# CH32V002F4P6.net
KiCad netlist of a schematic drawn in Altium Designer
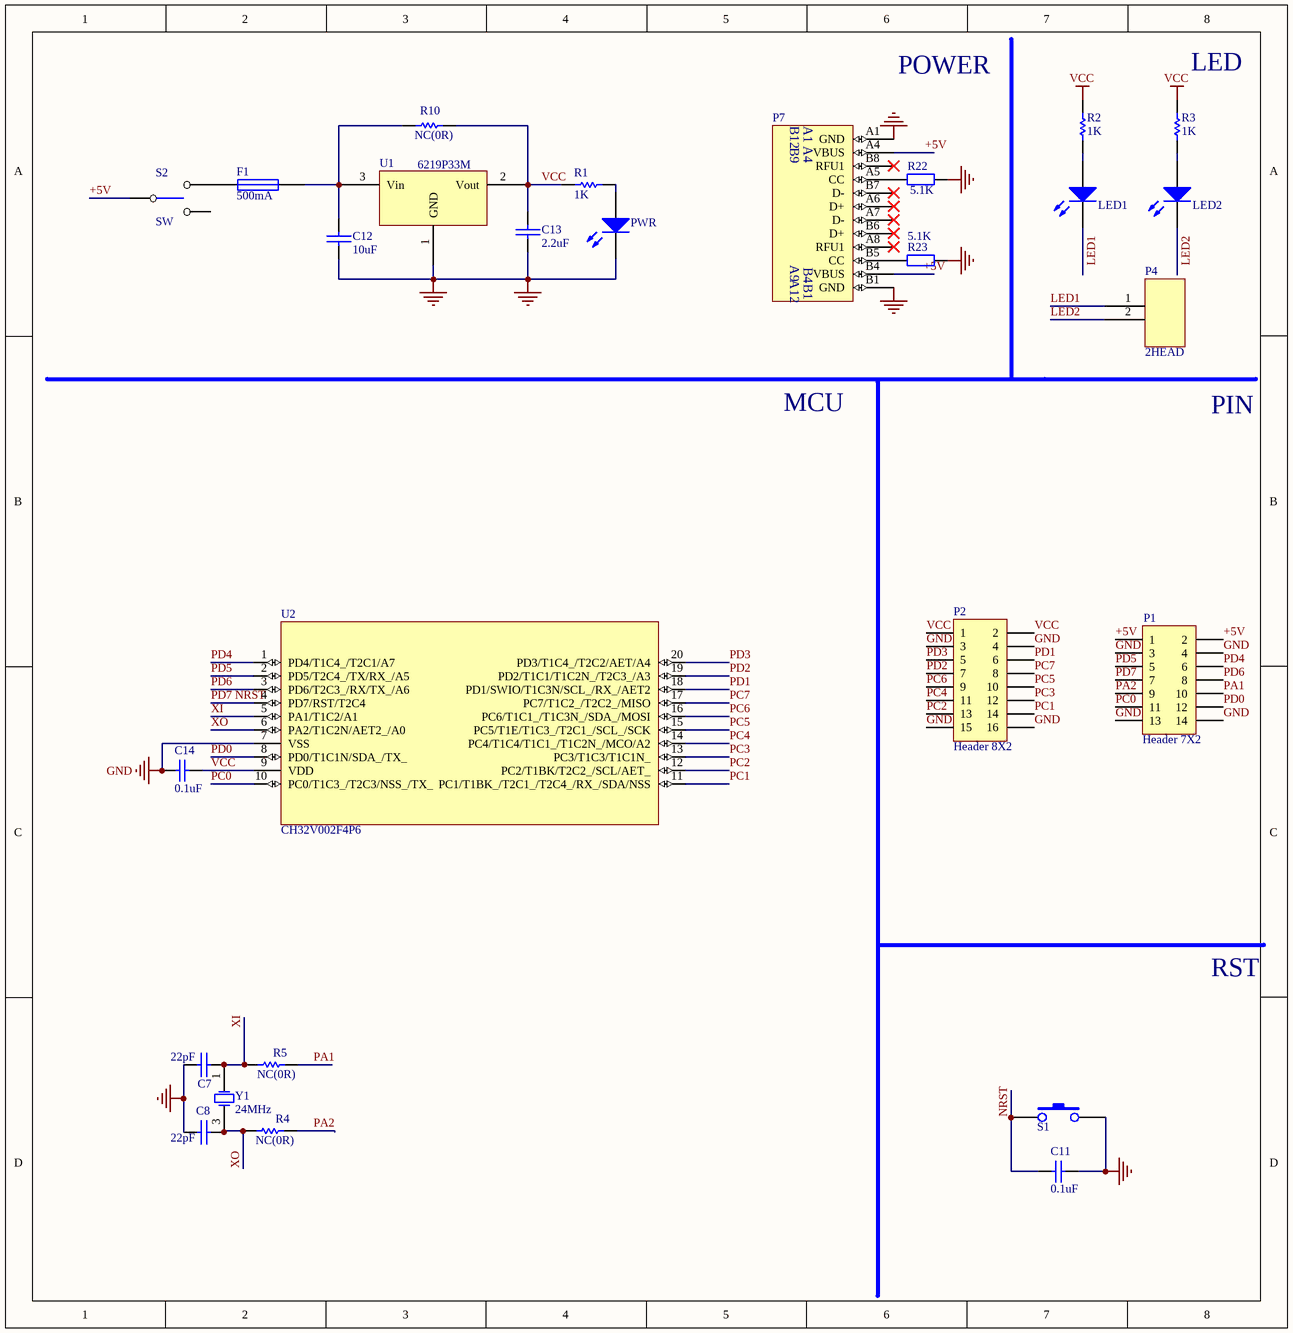
[diagram p0: CH32V002F4P6.SchDoc]

(export (version "E")
  (design (tool "Eeschema 10.0.6"))
  (components
    (comp (ref "C7")
      (value "22pF")
      (footprint "0402_C")
      (description "Capacitor")
      (libsource (lib "*") (part "CAP"))
    )
    (comp (ref "C8")
      (value "22pF")
      (footprint "0402_C")
      (description "Capacitor")
      (libsource (lib "*") (part "CAP"))
    )
    (comp (ref "C11")
      (value "0.1uF")
      (footprint "0402_C")
      (description "Capacitor")
      (fields (field (name "PUBLISHER") "Altium Limited"))
      (libsource (lib "*") (part "Cap"))
    )
    (comp (ref "C12")
      (value "10uF")
      (footprint "0603_C")
      (description "Capacitor")
      (libsource (lib "wch_sch_others") (part "CAP"))
    )
    (comp (ref "C13")
      (value "2.2uF")
      (footprint "0402_C")
      (description "Capacitor")
      (libsource (lib "wch_sch_others") (part "CAP"))
    )
    (comp (ref "C14")
      (value "0.1uF")
      (footprint "0603_C")
      (description "Capacitor")
      (fields (field (name "PUBLISHER") "Altium Limited"))
      (libsource (lib "*") (part "Cap"))
    )
    (comp (ref "F1")
      (value "500mA")
      (footprint "0603")
      (description "Fuse")
      (libsource (lib "*") (part "FUSE1"))
    )
    (comp (ref "LED1")
      (value "LED1   blue")
      (footprint "0603+")
      (description "Typical INFRARED GaAs LED")
      (fields (field (name "PUBLISHER") "Altium Limited"))
      (libsource (lib "*") (part "LED0"))
    )
    (comp (ref "LED2")
      (value "LED2  blue")
      (footprint "0603+")
      (description "Typical INFRARED GaAs LED")
      (fields (field (name "PUBLISHER") "Altium Limited"))
      (libsource (lib "*") (part "LED0"))
    )
    (comp (ref "P1")
      (value "Header 7X2")
      (footprint "HDR2X7")
      (description "Header, 7-Pin, Dual row")
      (fields (field (name "PUBLISHER") "Altium Limited"))
      (libsource (lib "Miscellaneous Connectors") (part "Header 7X2"))
    )
    (comp (ref "P2")
      (value "Header 8X2")
      (footprint "HDR2X8")
      (description "Header, 8-Pin, Dual row")
      (fields (field (name "PUBLISHER") "Altium Limited"))
      (libsource (lib "Miscellaneous Connectors") (part "Header 8X2"))
    )
    (comp (ref "P4") (value "2HEAD") (footprint "SIP2-2.54mm") (libsource (lib "*") (part "2HEAD")))
    (comp (ref "P7")
      (value "TYPE-C")
      (footprint "TYPE-C-Receptacle-2.0")
      (libsource (lib "*") (part "TYPE-C1"))
    )
    (comp (ref "PWR")
      (value "POWER  red")
      (footprint "0603+")
      (description "Typical INFRARED GaAs LED")
      (fields (field (name "PUBLISHER") "Altium Limited"))
      (libsource (lib "") (part "LED0_1"))
    )
    (comp (ref "R1")
      (value "1K")
      (footprint "0402")
      (description "Semiconductor Resistor")
      (fields (field (name "PUBLISHER") "Altium Limited"))
      (libsource (lib "*") (part "Res Semi"))
    )
    (comp (ref "R2")
      (value "1K")
      (footprint "0402")
      (description "Semiconductor Resistor")
      (fields (field (name "PUBLISHER") "Altium Limited"))
      (libsource (lib "*") (part "Res Semi"))
    )
    (comp (ref "R3")
      (value "1K")
      (footprint "0402")
      (description "Semiconductor Resistor")
      (fields (field (name "PUBLISHER") "Altium Limited"))
      (libsource (lib "*") (part "Res Semi"))
    )
    (comp (ref "R4")
      (value "NC(0R)")
      (footprint "0402")
      (description "Semiconductor Resistor")
      (fields (field (name "Comment") "0R") (field (name "PUBLISHER") "Altium Limited"))
      (libsource (lib "*") (part "Res Semi"))
    )
    (comp (ref "R5")
      (value "NC(0R)")
      (footprint "0402")
      (description "Semiconductor Resistor")
      (fields (field (name "Comment") "0R") (field (name "PUBLISHER") "Altium Limited"))
      (libsource (lib "*") (part "Res Semi"))
    )
    (comp (ref "R10")
      (value "NC(0R)")
      (footprint "0402")
      (description "Semiconductor Resistor")
      (fields (field (name "Comment") "0R") (field (name "PUBLISHER") "Altium Limited"))
      (libsource (lib "*") (part "Res Semi"))
    )
    (comp (ref "R22")
      (value "5.1K")
      (footprint "0402")
      (description "Resistor")
      (libsource (lib "Miscellaneous Devices") (part "Res2"))
    )
    (comp (ref "R23")
      (value "5.1K")
      (footprint "0402")
      (description "Resistor")
      (libsource (lib "Miscellaneous Devices") (part "Res2"))
    )
    (comp (ref "S1") (value "NRST") (footprint "SMD_6.1x3.65x2.5mm-KEY") (libsource (lib "*") (part "KEY")))
    (comp (ref "S2") (value "SW") (footprint "SW1") (libsource (lib "*") (part "SW")))
    (comp (ref "U1")
      (value "6219P33M")
      (footprint "SOT-23")
      (libsource (lib "wch_sch_others") (part "6219P33M"))
    )
    (comp (ref "U2")
      (value "CH32V002F4P6")
      (footprint "TSSOP20")
      (description "RISC-V MCU, 48MHz, ADC/UART/I2C/SPI")
      (libsource (lib "DHXXXSCH") (part "CH32V002F4P6"))
    )
    (comp (ref "Y1")
      (value "24MHz")
      (footprint "XT3225")
      (description "Crystal Oscillator")
      (fields (field (name "PUBLISHER") "Altium Limited"))
      (libsource (lib "*") (part "XTAL"))
    )
  )
  (nets
    (net (code "1") (name "/+5V") (class "Default")
      (node (ref "P1") (pin "1") (pinfunction "1_1") (pintype "passive"))
      (node (ref "P1") (pin "2") (pinfunction "2_2") (pintype "passive"))
      (node (ref "P7") (pin "A4") (pinfunction "VBUS_A4") (pintype "bidirectional"))
      (node (ref "P7") (pin "B4") (pinfunction "VBUS_B4") (pintype "bidirectional"))
      (node (ref "S2") (pin "1") (pinfunction "1_1") (pintype "passive"))
    )
    (net (code "2") (name "/LED1") (class "Default")
      (node (ref "LED1") (pin "2") (pinfunction "K_2") (pintype "passive"))
      (node (ref "P4") (pin "1") (pintype "passive"))
    )
    (net (code "3") (name "/LED2") (class "Default")
      (node (ref "LED2") (pin "2") (pinfunction "K_2") (pintype "passive"))
      (node (ref "P4") (pin "2") (pintype "passive"))
    )
    (net (code "4") (name "/NRST") (class "Default")
      (node (ref "C11") (pin "2") (pinfunction "2_2") (pintype "passive"))
      (node (ref "P1") (pin "7") (pinfunction "7_7") (pintype "passive"))
      (node (ref "S1") (pin "1") (pinfunction "1_1") (pintype "passive"))
      (node (ref "U2") (pin "4") (pinfunction "PD7/RST/T2C4_4") (pintype "bidirectional"))
    )
    (net (code "5") (name "/PA1") (class "Default")
      (node (ref "P1") (pin "10") (pinfunction "10_10") (pintype "passive"))
      (node (ref "R5") (pin "2") (pinfunction "2_2") (pintype "passive"))
    )
    (net (code "6") (name "/PA2") (class "Default")
      (node (ref "P1") (pin "9") (pinfunction "9_9") (pintype "passive"))
      (node (ref "R4") (pin "2") (pinfunction "2_2") (pintype "passive"))
    )
    (net (code "7") (name "/PC0") (class "Default")
      (node (ref "P1") (pin "11") (pinfunction "11_11") (pintype "passive"))
      (node (ref "U2") (pin "10") (pinfunction "PC0/T1C3_/T2C3/NSS_/TX__10") (pintype "bidirectional"))
    )
    (net (code "8") (name "/PC1") (class "Default")
      (node (ref "P2") (pin "14") (pinfunction "14_14") (pintype "passive"))
      (node (ref "U2") (pin "11") (pinfunction "PC1/T1BK_/T2C1_/T2C4_/RX_/SDA/NSS_11") (pintype "bidirectional"))
    )
    (net (code "9") (name "/PC2") (class "Default")
      (node (ref "P2") (pin "13") (pinfunction "13_13") (pintype "passive"))
      (node (ref "U2") (pin "12") (pinfunction "PC2/T1BK/T2C2_/SCL/AET__12") (pintype "bidirectional"))
    )
    (net (code "10") (name "/PC3") (class "Default")
      (node (ref "P2") (pin "12") (pinfunction "12_12") (pintype "passive"))
      (node (ref "U2") (pin "13") (pinfunction "PC3/T1C3/T1C1N__13") (pintype "bidirectional"))
    )
    (net (code "11") (name "/PC4") (class "Default")
      (node (ref "P2") (pin "11") (pinfunction "11_11") (pintype "passive"))
      (node (ref "U2") (pin "14") (pinfunction "PC4/T1C4/T1C1_/T1C2N_/MCO/A2_14") (pintype "bidirectional"))
    )
    (net (code "12") (name "/PC5") (class "Default")
      (node (ref "P2") (pin "10") (pinfunction "10_10") (pintype "passive"))
      (node (ref "U2") (pin "15") (pinfunction "PC5/T1E/T1C3_/T2C1_/SCL_/SCK_15") (pintype "bidirectional"))
    )
    (net (code "13") (name "/PC6") (class "Default")
      (node (ref "P2") (pin "9") (pinfunction "9_9") (pintype "passive"))
      (node (ref "U2") (pin "16") (pinfunction "PC6/T1C1_/T1C3N_/SDA_/MOSI_16") (pintype "bidirectional"))
    )
    (net (code "14") (name "/PC7") (class "Default")
      (node (ref "P2") (pin "8") (pinfunction "8_8") (pintype "passive"))
      (node (ref "U2") (pin "17") (pinfunction "PC7/T1C2_/T2C2_/MISO_17") (pintype "bidirectional"))
    )
    (net (code "15") (name "/PD0") (class "Default")
      (node (ref "P1") (pin "12") (pinfunction "12_12") (pintype "passive"))
      (node (ref "U2") (pin "8") (pinfunction "PD0/T1C1N/SDA_/TX__8") (pintype "bidirectional"))
    )
    (net (code "16") (name "/PD1") (class "Default")
      (node (ref "P2") (pin "6") (pinfunction "6_6") (pintype "passive"))
      (node (ref "U2") (pin "18") (pinfunction "PD1/SWIO/T1C3N/SCL_/RX_/AET2_18") (pintype "bidirectional"))
    )
    (net (code "17") (name "/PD2") (class "Default")
      (node (ref "P2") (pin "7") (pinfunction "7_7") (pintype "passive"))
      (node (ref "U2") (pin "19") (pinfunction "PD2/T1C1/T1C2N_/T2C3_/A3_19") (pintype "bidirectional"))
    )
    (net (code "18") (name "/PD3") (class "Default")
      (node (ref "P2") (pin "5") (pinfunction "5_5") (pintype "passive"))
      (node (ref "U2") (pin "20") (pinfunction "PD3/T1C4_/T2C2/AET/A4_20") (pintype "bidirectional"))
    )
    (net (code "19") (name "/PD4") (class "Default")
      (node (ref "P1") (pin "6") (pinfunction "6_6") (pintype "passive"))
      (node (ref "U2") (pin "1") (pinfunction "PD4/T1C4_/T2C1/A7_1") (pintype "bidirectional"))
    )
    (net (code "20") (name "/PD5") (class "Default")
      (node (ref "P1") (pin "5") (pinfunction "5_5") (pintype "passive"))
      (node (ref "U2") (pin "2") (pinfunction "PD5/T2C4_/TX/RX_/A5_2") (pintype "bidirectional"))
    )
    (net (code "21") (name "/PD6") (class "Default")
      (node (ref "P1") (pin "8") (pinfunction "8_8") (pintype "passive"))
      (node (ref "U2") (pin "3") (pinfunction "PD6/T2C3_/RX/TX_/A6_3") (pintype "bidirectional"))
    )
    (net (code "22") (name "/XI") (class "Default")
      (node (ref "C7") (pin "2") (pinfunction "2_2") (pintype "passive"))
      (node (ref "R5") (pin "1") (pinfunction "1_1") (pintype "passive"))
      (node (ref "U2") (pin "5") (pinfunction "PA1/T1C2/A1_5") (pintype "bidirectional"))
      (node (ref "Y1") (pin "1") (pinfunction "OSC1_1") (pintype "passive"))
    )
    (net (code "23") (name "/XO") (class "Default")
      (node (ref "C8") (pin "2") (pinfunction "2_2") (pintype "passive"))
      (node (ref "R4") (pin "1") (pinfunction "1_1") (pintype "passive"))
      (node (ref "U2") (pin "6") (pinfunction "PA2/T1C2N/AET2_/A0_6") (pintype "bidirectional"))
      (node (ref "Y1") (pin "3") (pinfunction "OSC2_3") (pintype "passive"))
    )
    (net (code "24") (name "GND") (class "Default")
      (node (ref "C11") (pin "1") (pinfunction "1_1") (pintype "passive"))
      (node (ref "C12") (pin "2") (pinfunction "2_2") (pintype "passive"))
      (node (ref "C13") (pin "1") (pinfunction "1_1") (pintype "passive"))
      (node (ref "C14") (pin "2") (pinfunction "2_2") (pintype "passive"))
      (node (ref "C7") (pin "1") (pinfunction "1_1") (pintype "passive"))
      (node (ref "C8") (pin "1") (pinfunction "1_1") (pintype "passive"))
      (node (ref "P1") (pin "13") (pinfunction "13_13") (pintype "passive"))
      (node (ref "P1") (pin "14") (pinfunction "14_14") (pintype "passive"))
      (node (ref "P1") (pin "3") (pinfunction "3_3") (pintype "passive"))
      (node (ref "P1") (pin "4") (pinfunction "4_4") (pintype "passive"))
      (node (ref "P2") (pin "15") (pinfunction "15_15") (pintype "passive"))
      (node (ref "P2") (pin "16") (pinfunction "16_16") (pintype "passive"))
      (node (ref "P2") (pin "3") (pinfunction "3_3") (pintype "passive"))
      (node (ref "P2") (pin "4") (pinfunction "4_4") (pintype "passive"))
      (node (ref "P7") (pin "A1") (pinfunction "GND_A1") (pintype "bidirectional"))
      (node (ref "P7") (pin "B1") (pinfunction "GND_B1") (pintype "bidirectional"))
      (node (ref "PWR") (pin "2") (pinfunction "K_2") (pintype "passive"))
      (node (ref "R22") (pin "2") (pinfunction "2_2") (pintype "passive"))
      (node (ref "R23") (pin "2") (pinfunction "2_2") (pintype "passive"))
      (node (ref "S1") (pin "2") (pinfunction "2_2") (pintype "passive"))
      (node (ref "U1") (pin "1") (pinfunction "GND_1") (pintype "passive"))
      (node (ref "U2") (pin "7") (pinfunction "VSS_7") (pintype "power_in"))
    )
    (net (code "25") (name "Net-(F1-Pad1)") (class "Default")
      (node (ref "F1") (pin "1") (pinfunction "1_1") (pintype "passive"))
      (node (ref "S2") (pin "3") (pinfunction "3_3") (pintype "passive"))
    )
    (net (code "26") (name "Net-(LED1-A)") (class "Default")
      (node (ref "LED1") (pin "1") (pinfunction "A_1") (pintype "passive"))
      (node (ref "R2") (pin "2") (pinfunction "2_2") (pintype "passive"))
    )
    (net (code "27") (name "Net-(LED2-A)") (class "Default")
      (node (ref "LED2") (pin "1") (pinfunction "A_1") (pintype "passive"))
      (node (ref "R3") (pin "2") (pinfunction "2_2") (pintype "passive"))
    )
    (net (code "28") (name "Net-(P7-CC-PadA5)") (class "Default")
      (node (ref "P7") (pin "A5") (pinfunction "CC_A5") (pintype "bidirectional"))
      (node (ref "R22") (pin "1") (pinfunction "1_1") (pintype "passive"))
    )
    (net (code "29") (name "Net-(P7-CC-PadB5)") (class "Default")
      (node (ref "P7") (pin "B5") (pinfunction "CC_B5") (pintype "bidirectional"))
      (node (ref "R23") (pin "1") (pinfunction "1_1") (pintype "passive"))
    )
    (net (code "30") (name "Net-(PWR-A)") (class "Default")
      (node (ref "PWR") (pin "1") (pinfunction "A_1") (pintype "passive"))
      (node (ref "R1") (pin "1") (pinfunction "1_1") (pintype "passive"))
    )
    (net (code "31") (name "Net-(U1-Vin)") (class "Default")
      (node (ref "C12") (pin "1") (pinfunction "1_1") (pintype "passive"))
      (node (ref "F1") (pin "2") (pinfunction "2_2") (pintype "passive"))
      (node (ref "R10") (pin "1") (pinfunction "1_1") (pintype "passive"))
      (node (ref "U1") (pin "3") (pinfunction "Vin_3") (pintype "passive"))
    )
    (net (code "32") (name "VCC") (class "Default")
      (node (ref "C13") (pin "2") (pinfunction "2_2") (pintype "passive"))
      (node (ref "C14") (pin "1") (pinfunction "1_1") (pintype "passive"))
      (node (ref "P2") (pin "1") (pinfunction "1_1") (pintype "passive"))
      (node (ref "P2") (pin "2") (pinfunction "2_2") (pintype "passive"))
      (node (ref "R1") (pin "2") (pinfunction "2_2") (pintype "passive"))
      (node (ref "R10") (pin "2") (pinfunction "2_2") (pintype "passive"))
      (node (ref "R2") (pin "1") (pinfunction "1_1") (pintype "passive"))
      (node (ref "R3") (pin "1") (pinfunction "1_1") (pintype "passive"))
      (node (ref "U1") (pin "2") (pinfunction "Vout_2") (pintype "passive"))
      (node (ref "U2") (pin "9") (pinfunction "VDD_9") (pintype "power_in"))
    )
    (net (code "33") (name "unconnected-(P7-D+-PadA6)") (class "Default")
      (node (ref "P7") (pin "A6") (pinfunction "D+_A6") (pintype "bidirectional+no_connect"))
    )
    (net (code "34") (name "unconnected-(P7-D+-PadB6)") (class "Default")
      (node (ref "P7") (pin "B6") (pinfunction "D+_B6") (pintype "bidirectional+no_connect"))
    )
    (net (code "35") (name "unconnected-(P7-D--PadA7)") (class "Default")
      (node (ref "P7") (pin "A7") (pinfunction "D-_A7") (pintype "bidirectional+no_connect"))
    )
    (net (code "36") (name "unconnected-(P7-D--PadB7)") (class "Default")
      (node (ref "P7") (pin "B7") (pinfunction "D-_B7") (pintype "bidirectional+no_connect"))
    )
    (net (code "37") (name "unconnected-(P7-RFU1-PadA8)") (class "Default")
      (node (ref "P7") (pin "A8") (pinfunction "RFU1_A8") (pintype "bidirectional+no_connect"))
    )
    (net (code "38") (name "unconnected-(P7-RFU1-PadB8)") (class "Default")
      (node (ref "P7") (pin "B8") (pinfunction "RFU1_B8") (pintype "bidirectional+no_connect"))
    )
    (net (code "39") (name "unconnected-(S2-Pad2)") (class "Default")
      (node (ref "S2") (pin "2") (pinfunction "2_2") (pintype "passive"))
    )
  )
)
